# AudioADC.net
KiCad netlist of a schematic drawn in Altium Designer
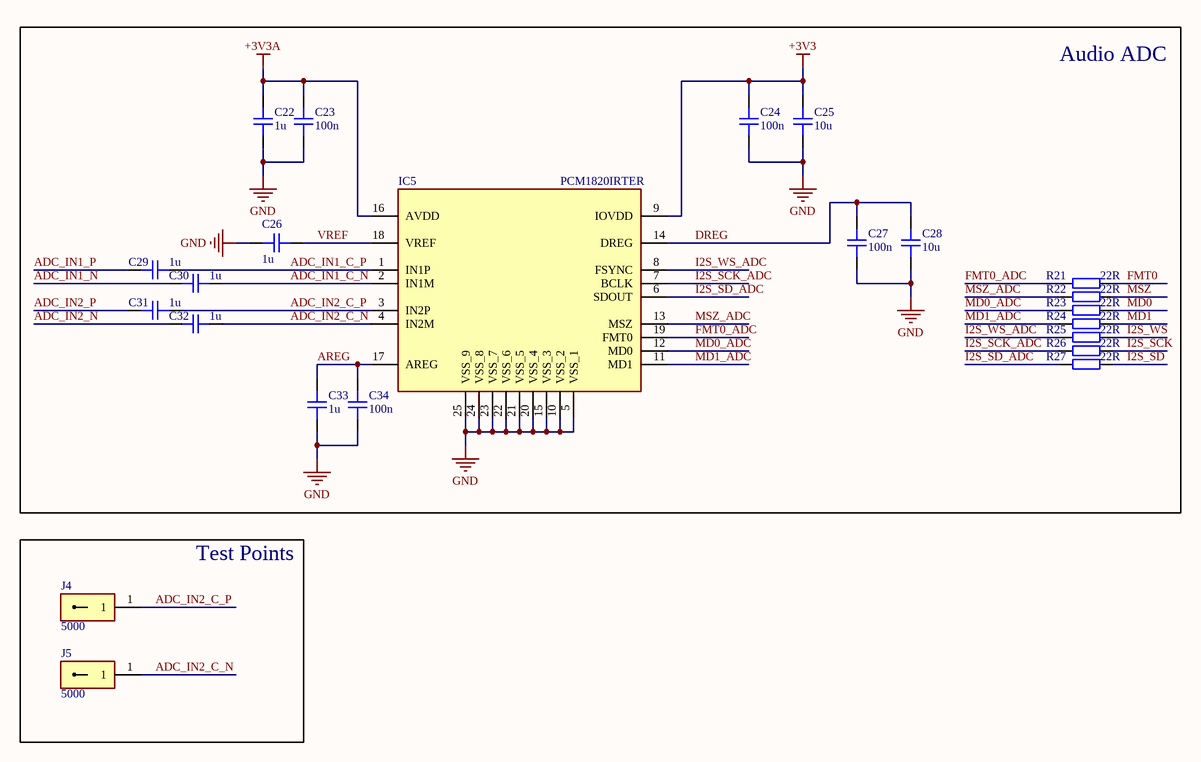
[diagram p0: AudioADC.SchDoc]

(export (version "E")
  (design (tool "Eeschema 10.0.6"))
  (components
    (comp (ref "C22")
      (value "1u")
      (footprint "CAP_0603")
      (description "Capacitor SMD 0603")
      (libsource (lib "Schematic-Lib-PhilsLab") (part "CAP_0603"))
    )
    (comp (ref "C23")
      (value "100n")
      (footprint "CAP_0402")
      (description "Capacitor SMD 0402")
      (libsource (lib "Schematic-Lib-PhilsLab") (part "CAP_0402"))
    )
    (comp (ref "C24")
      (value "100n")
      (footprint "CAP_0402")
      (description "Capacitor SMD 0402")
      (libsource (lib "Schematic-Lib-PhilsLab") (part "CAP_0402"))
    )
    (comp (ref "C25")
      (value "10u")
      (footprint "CAP_0603")
      (description "Capacitor SMD 0603")
      (libsource (lib "Schematic-Lib-PhilsLab") (part "CAP_0603"))
    )
    (comp (ref "C26")
      (value "1u")
      (footprint "CAP_0402")
      (description "Capacitor SMD 0402")
      (libsource (lib "Schematic-Lib-PhilsLab") (part "CAP_0402"))
    )
    (comp (ref "C27")
      (value "100n")
      (footprint "CAP_0402")
      (description "Capacitor SMD 0402")
      (libsource (lib "Schematic-Lib-PhilsLab") (part "CAP_0402"))
    )
    (comp (ref "C28")
      (value "10u")
      (footprint "CAP_0603")
      (description "Capacitor SMD 0603")
      (libsource (lib "Schematic-Lib-PhilsLab") (part "CAP_0603"))
    )
    (comp (ref "C29")
      (value "1u")
      (footprint "CAP_0402")
      (description "Capacitor SMD 0402")
      (libsource (lib "Schematic-Lib-PhilsLab") (part "CAP_0402"))
    )
    (comp (ref "C30")
      (value "1u")
      (footprint "CAP_0402")
      (description "Capacitor SMD 0402")
      (libsource (lib "Schematic-Lib-PhilsLab") (part "CAP_0402"))
    )
    (comp (ref "C31")
      (value "1u")
      (footprint "CAP_0402")
      (description "Capacitor SMD 0402")
      (libsource (lib "Schematic-Lib-PhilsLab") (part "CAP_0402"))
    )
    (comp (ref "C32")
      (value "1u")
      (footprint "CAP_0402")
      (description "Capacitor SMD 0402")
      (libsource (lib "Schematic-Lib-PhilsLab") (part "CAP_0402"))
    )
    (comp (ref "C33")
      (value "1u")
      (footprint "CAP_0603")
      (description "Capacitor SMD 0603")
      (libsource (lib "Schematic-Lib-PhilsLab") (part "CAP_0603"))
    )
    (comp (ref "C34")
      (value "100n")
      (footprint "CAP_0402")
      (description "Capacitor SMD 0402")
      (libsource (lib "Schematic-Lib-PhilsLab") (part "CAP_0402"))
    )
    (comp (ref "IC5")
      (value "PCM1820IRTER")
      (footprint "BAT_Detector_PCBLib:PCM1820IRTER")
      (description "Integrated Circuit")
      (fields (field (name "MOUSER PART NUMBER") "595-PCM1820IRTER"))
      (libsource (lib "BAT_Detector_SCHLib") (part "PCM1820IRTER"))
    )
    (comp (ref "J4")
      (value "5000")
      (footprint "BAT_Detector_PCBLib:5000")
      (description "Connector")
      (fields (field (name "MOUSER PART NUMBER") "534-5000"))
      (libsource (lib "BAT_Detector_SCHLib") (part "5000"))
    )
    (comp (ref "J5")
      (value "5000")
      (footprint "BAT_Detector_PCBLib:5000")
      (description "Connector")
      (fields (field (name "MOUSER PART NUMBER") "534-5000"))
      (libsource (lib "BAT_Detector_SCHLib") (part "5000"))
    )
    (comp (ref "R21")
      (value "22R")
      (footprint "RES_0402")
      (description "Resistor SMD 0402")
      (libsource (lib "Schematic-Lib-PhilsLab") (part "RES_0402"))
    )
    (comp (ref "R22")
      (value "22R")
      (footprint "RES_0402")
      (description "Resistor SMD 0402")
      (libsource (lib "Schematic-Lib-PhilsLab") (part "RES_0402"))
    )
    (comp (ref "R23")
      (value "22R")
      (footprint "RES_0402")
      (description "Resistor SMD 0402")
      (libsource (lib "Schematic-Lib-PhilsLab") (part "RES_0402"))
    )
    (comp (ref "R24")
      (value "22R")
      (footprint "RES_0402")
      (description "Resistor SMD 0402")
      (libsource (lib "Schematic-Lib-PhilsLab") (part "RES_0402"))
    )
    (comp (ref "R25")
      (value "22R")
      (footprint "RES_0402")
      (description "Resistor SMD 0402")
      (libsource (lib "Schematic-Lib-PhilsLab") (part "RES_0402"))
    )
    (comp (ref "R26")
      (value "22R")
      (footprint "RES_0402")
      (description "Resistor SMD 0402")
      (libsource (lib "Schematic-Lib-PhilsLab") (part "RES_0402"))
    )
    (comp (ref "R27")
      (value "22R")
      (footprint "RES_0402")
      (description "Resistor SMD 0402")
      (libsource (lib "Schematic-Lib-PhilsLab") (part "RES_0402"))
    )
  )
  (nets
    (net (code "1") (name "+3V3") (class "Default")
      (node (ref "C24") (pin "2") (pinfunction "2_2") (pintype "passive"))
      (node (ref "C25") (pin "2") (pinfunction "2_2") (pintype "passive"))
      (node (ref "IC5") (pin "9") (pinfunction "IOVDD_9") (pintype "passive"))
    )
    (net (code "2") (name "+3V3A") (class "Default")
      (node (ref "C22") (pin "2") (pinfunction "2_2") (pintype "passive"))
      (node (ref "C23") (pin "2") (pinfunction "2_2") (pintype "passive"))
      (node (ref "IC5") (pin "16") (pinfunction "AVDD_16") (pintype "passive"))
    )
    (net (code "3") (name "/ADC_IN1_C_N") (class "Default")
      (node (ref "C30") (pin "2") (pinfunction "2_2") (pintype "passive"))
      (node (ref "IC5") (pin "2") (pinfunction "IN1M_2") (pintype "passive"))
    )
    (net (code "4") (name "/ADC_IN1_C_P") (class "Default")
      (node (ref "C29") (pin "2") (pinfunction "2_2") (pintype "passive"))
      (node (ref "IC5") (pin "1") (pinfunction "IN1P_1") (pintype "passive"))
    )
    (net (code "5") (name "/ADC_IN1_N") (class "Default")
      (node (ref "C30") (pin "1") (pinfunction "1_1") (pintype "passive"))
    )
    (net (code "6") (name "/ADC_IN1_P") (class "Default")
      (node (ref "C29") (pin "1") (pinfunction "1_1") (pintype "passive"))
    )
    (net (code "7") (name "/ADC_IN2_C_N") (class "Default")
      (node (ref "C32") (pin "2") (pinfunction "2_2") (pintype "passive"))
      (node (ref "IC5") (pin "4") (pinfunction "IN2M_4") (pintype "passive"))
      (node (ref "J5") (pin "1") (pinfunction "1_1") (pintype "passive"))
    )
    (net (code "8") (name "/ADC_IN2_C_P") (class "Default")
      (node (ref "C31") (pin "2") (pinfunction "2_2") (pintype "passive"))
      (node (ref "IC5") (pin "3") (pinfunction "IN2P_3") (pintype "passive"))
      (node (ref "J4") (pin "1") (pinfunction "1_1") (pintype "passive"))
    )
    (net (code "9") (name "/ADC_IN2_N") (class "Default")
      (node (ref "C32") (pin "1") (pinfunction "1_1") (pintype "passive"))
    )
    (net (code "10") (name "/ADC_IN2_P") (class "Default")
      (node (ref "C31") (pin "1") (pinfunction "1_1") (pintype "passive"))
    )
    (net (code "11") (name "/AREG") (class "Default")
      (node (ref "C33") (pin "2") (pinfunction "2_2") (pintype "passive"))
      (node (ref "C34") (pin "2") (pinfunction "2_2") (pintype "passive"))
      (node (ref "IC5") (pin "17") (pinfunction "AREG_17") (pintype "passive"))
    )
    (net (code "12") (name "/DREG") (class "Default")
      (node (ref "C27") (pin "2") (pinfunction "2_2") (pintype "passive"))
      (node (ref "C28") (pin "2") (pinfunction "2_2") (pintype "passive"))
      (node (ref "IC5") (pin "14") (pinfunction "DREG_14") (pintype "passive"))
    )
    (net (code "13") (name "/FMT0") (class "Default")
      (node (ref "R21") (pin "2") (pinfunction "2_2") (pintype "passive"))
    )
    (net (code "14") (name "/FMT0_ADC") (class "Default")
      (node (ref "IC5") (pin "19") (pinfunction "FMT0_19") (pintype "passive"))
      (node (ref "R21") (pin "1") (pinfunction "1_1") (pintype "passive"))
    )
    (net (code "15") (name "/I2S_SCK") (class "Default")
      (node (ref "R26") (pin "2") (pinfunction "2_2") (pintype "passive"))
    )
    (net (code "16") (name "/I2S_SCK_ADC") (class "Default")
      (node (ref "IC5") (pin "7") (pinfunction "BCLK_7") (pintype "passive"))
      (node (ref "R26") (pin "1") (pinfunction "1_1") (pintype "passive"))
    )
    (net (code "17") (name "/I2S_SD") (class "Default")
      (node (ref "R27") (pin "2") (pinfunction "2_2") (pintype "passive"))
    )
    (net (code "18") (name "/I2S_SD_ADC") (class "Default")
      (node (ref "IC5") (pin "6") (pinfunction "SDOUT_6") (pintype "passive"))
      (node (ref "R27") (pin "1") (pinfunction "1_1") (pintype "passive"))
    )
    (net (code "19") (name "/I2S_WS") (class "Default")
      (node (ref "R25") (pin "2") (pinfunction "2_2") (pintype "passive"))
    )
    (net (code "20") (name "/I2S_WS_ADC") (class "Default")
      (node (ref "IC5") (pin "8") (pinfunction "FSYNC_8") (pintype "passive"))
      (node (ref "R25") (pin "1") (pinfunction "1_1") (pintype "passive"))
    )
    (net (code "21") (name "/MD0") (class "Default")
      (node (ref "R23") (pin "2") (pinfunction "2_2") (pintype "passive"))
    )
    (net (code "22") (name "/MD0_ADC") (class "Default")
      (node (ref "IC5") (pin "12") (pinfunction "MD0_12") (pintype "passive"))
      (node (ref "R23") (pin "1") (pinfunction "1_1") (pintype "passive"))
    )
    (net (code "23") (name "/MD1") (class "Default")
      (node (ref "R24") (pin "2") (pinfunction "2_2") (pintype "passive"))
    )
    (net (code "24") (name "/MD1_ADC") (class "Default")
      (node (ref "IC5") (pin "11") (pinfunction "MD1_11") (pintype "passive"))
      (node (ref "R24") (pin "1") (pinfunction "1_1") (pintype "passive"))
    )
    (net (code "25") (name "/MSZ") (class "Default")
      (node (ref "R22") (pin "2") (pinfunction "2_2") (pintype "passive"))
    )
    (net (code "26") (name "/MSZ_ADC") (class "Default")
      (node (ref "IC5") (pin "13") (pinfunction "MSZ_13") (pintype "passive"))
      (node (ref "R22") (pin "1") (pinfunction "1_1") (pintype "passive"))
    )
    (net (code "27") (name "/VREF") (class "Default")
      (node (ref "C26") (pin "2") (pinfunction "2_2") (pintype "passive"))
      (node (ref "IC5") (pin "18") (pinfunction "VREF_18") (pintype "passive"))
    )
    (net (code "28") (name "GND") (class "Default")
      (node (ref "C22") (pin "1") (pinfunction "1_1") (pintype "passive"))
      (node (ref "C23") (pin "1") (pinfunction "1_1") (pintype "passive"))
      (node (ref "C24") (pin "1") (pinfunction "1_1") (pintype "passive"))
      (node (ref "C25") (pin "1") (pinfunction "1_1") (pintype "passive"))
      (node (ref "C26") (pin "1") (pinfunction "1_1") (pintype "passive"))
      (node (ref "C27") (pin "1") (pinfunction "1_1") (pintype "passive"))
      (node (ref "C28") (pin "1") (pinfunction "1_1") (pintype "passive"))
      (node (ref "C33") (pin "1") (pinfunction "1_1") (pintype "passive"))
      (node (ref "C34") (pin "1") (pinfunction "1_1") (pintype "passive"))
      (node (ref "IC5") (pin "10") (pinfunction "VSS_2_10") (pintype "passive"))
      (node (ref "IC5") (pin "15") (pinfunction "VSS_3_15") (pintype "passive"))
      (node (ref "IC5") (pin "20") (pinfunction "VSS_4_20") (pintype "passive"))
      (node (ref "IC5") (pin "21") (pinfunction "VSS_5_21") (pintype "passive"))
      (node (ref "IC5") (pin "22") (pinfunction "VSS_6_22") (pintype "passive"))
      (node (ref "IC5") (pin "23") (pinfunction "VSS_7_23") (pintype "passive"))
      (node (ref "IC5") (pin "24") (pinfunction "VSS_8_24") (pintype "passive"))
      (node (ref "IC5") (pin "25") (pinfunction "VSS_9_25") (pintype "passive"))
      (node (ref "IC5") (pin "5") (pinfunction "VSS_1_5") (pintype "passive"))
    )
  )
)
